# MainSch.net
KiCad netlist of a schematic drawn in Altium Designer
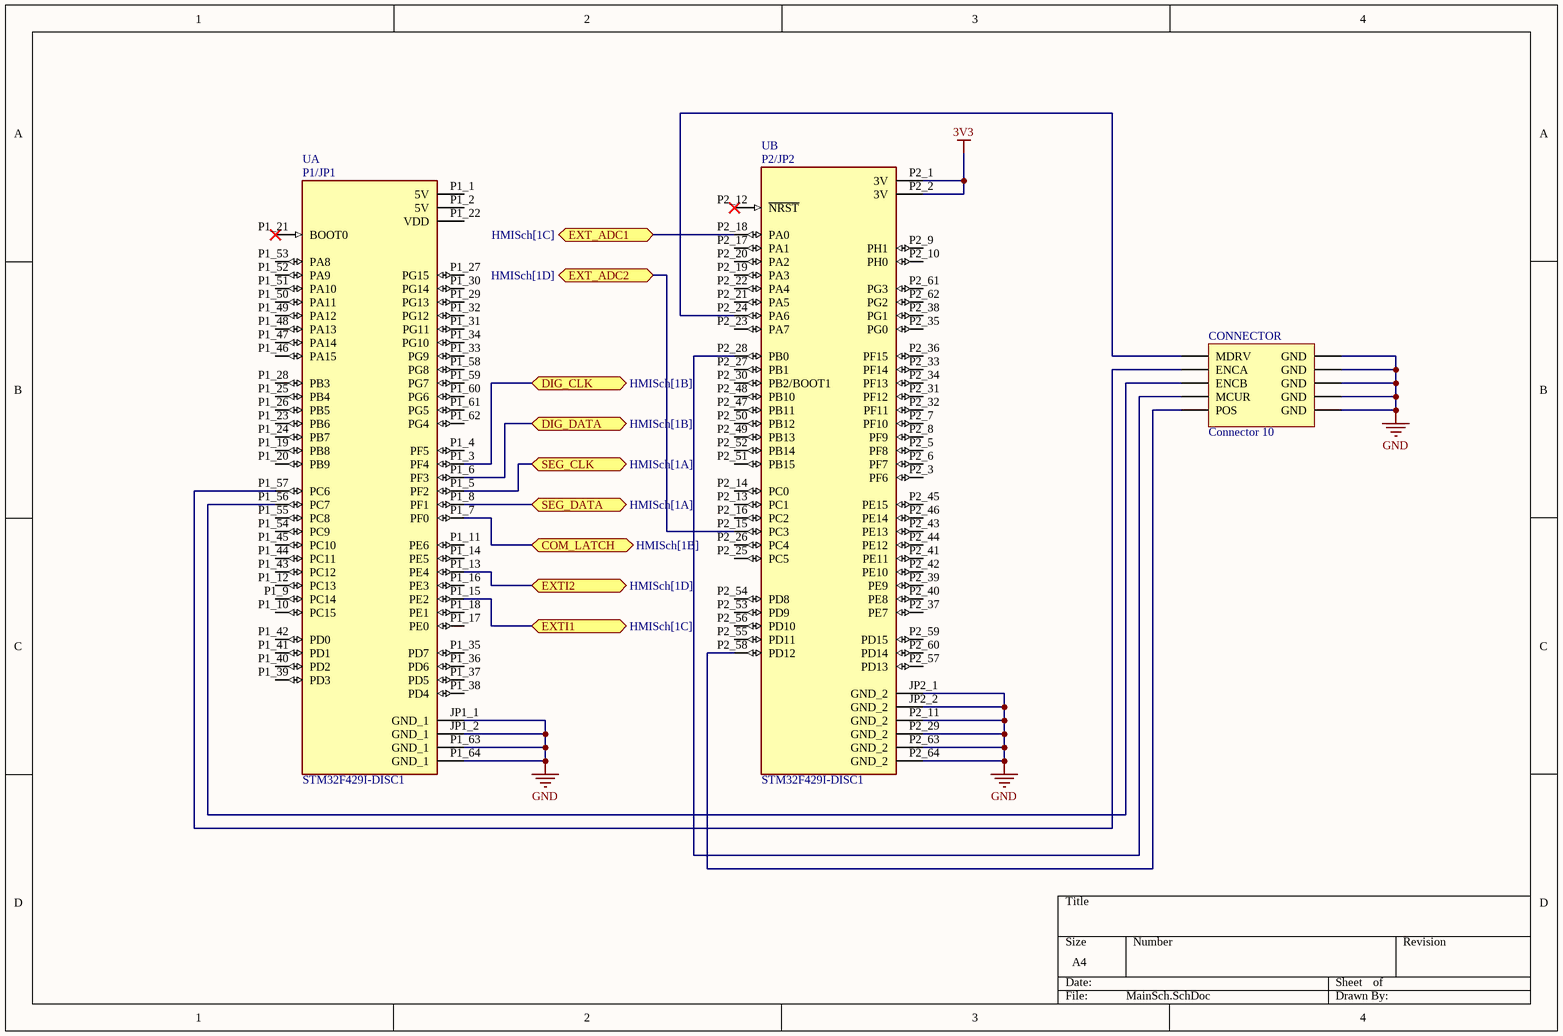
[diagram p0: MainSch.SchDoc]

(export (version "E")
  (design (tool "Eeschema 10.0.6"))
  (components
    (comp (ref "CONNECTOR")
      (value "Connector 10")
      (footprint "CONNECTOR-10P")
      (description "Special 10 pin ribbon connector")
      (libsource (lib "hallglib") (part "Connector 10 spec"))
    )
    (comp (ref "U")
      (value "STM32F429I-DISC1")
      (footprint "MODULE_STM32F429I-DISC1")
      (description "STM32F429 Discovery STM32F4 ARMÂ® CortexÂ®-M4 MCU 32-Bit Embedded Evaluation Board")
      (fields (field (name "MF") "STMicroelectronics"))
      (libsource (lib "SnapEDAsch") (part "STM32F429I-DISC1"))
    )
  )
  (nets
    (net (code "1") (name "/COM_LATCH") (class "Default")
      (node (ref "U") (pin "P1_7") (pinfunction "PF0_P1_7") (pintype "bidirectional"))
    )
    (net (code "2") (name "/DIG_CLK") (class "Default")
      (node (ref "U") (pin "P1_3") (pinfunction "PF4_P1_3") (pintype "bidirectional"))
    )
    (net (code "3") (name "/DIG_DATA") (class "Default")
      (node (ref "U") (pin "P1_6") (pinfunction "PF3_P1_6") (pintype "bidirectional"))
    )
    (net (code "4") (name "/EXTI1") (class "Default")
      (node (ref "U") (pin "P1_15") (pinfunction "PE2_P1_15") (pintype "bidirectional"))
    )
    (net (code "5") (name "/EXTI2") (class "Default")
      (node (ref "U") (pin "P1_13") (pinfunction "PE4_P1_13") (pintype "bidirectional"))
    )
    (net (code "6") (name "/EXT_ADC1") (class "Default")
      (node (ref "U") (pin "P2_18") (pinfunction "PA0_P2_18") (pintype "bidirectional"))
    )
    (net (code "7") (name "/EXT_ADC2") (class "Default")
      (node (ref "U") (pin "P2_15") (pinfunction "PC3_P2_15") (pintype "bidirectional"))
    )
    (net (code "8") (name "/SEG_CLK") (class "Default")
      (node (ref "U") (pin "P1_5") (pinfunction "PF2_P1_5") (pintype "bidirectional"))
    )
    (net (code "9") (name "/SEG_DATA") (class "Default")
      (node (ref "U") (pin "P1_8") (pinfunction "PF1_P1_8") (pintype "bidirectional"))
    )
    (net (code "10") (name "3V3") (class "Default")
      (node (ref "U") (pin "P2_1") (pinfunction "3V_P2_1") (pintype "power_in"))
      (node (ref "U") (pin "P2_2") (pinfunction "3V_P2_2") (pintype "power_in"))
    )
    (net (code "11") (name "GND") (class "Default")
      (node (ref "CONNECTOR") (pin "10") (pinfunction "GND_10") (pintype "passive"))
      (node (ref "CONNECTOR") (pin "2") (pinfunction "GND_2") (pintype "passive"))
      (node (ref "CONNECTOR") (pin "4") (pinfunction "GND_4") (pintype "passive"))
      (node (ref "CONNECTOR") (pin "6") (pinfunction "GND_6") (pintype "passive"))
      (node (ref "CONNECTOR") (pin "8") (pinfunction "GND_8") (pintype "passive"))
      (node (ref "U") (pin "JP1_1") (pinfunction "GND_1_JP1_1") (pintype "power_in"))
      (node (ref "U") (pin "JP1_2") (pinfunction "GND_1_JP1_2") (pintype "power_in"))
      (node (ref "U") (pin "JP2_1") (pinfunction "GND_2_JP2_1") (pintype "power_in"))
      (node (ref "U") (pin "JP2_2") (pinfunction "GND_2_JP2_2") (pintype "power_in"))
      (node (ref "U") (pin "P1_63") (pinfunction "GND_1_P1_63") (pintype "power_in"))
      (node (ref "U") (pin "P1_64") (pinfunction "GND_1_P1_64") (pintype "power_in"))
      (node (ref "U") (pin "P2_11") (pinfunction "GND_2_P2_11") (pintype "power_in"))
      (node (ref "U") (pin "P2_29") (pinfunction "GND_2_P2_29") (pintype "power_in"))
      (node (ref "U") (pin "P2_63") (pinfunction "GND_2_P2_63") (pintype "power_in"))
      (node (ref "U") (pin "P2_64") (pinfunction "GND_2_P2_64") (pintype "power_in"))
    )
    (net (code "12") (name "Net-(CONNECTOR-ENCA)") (class "Default")
      (node (ref "CONNECTOR") (pin "3") (pinfunction "ENCA_3") (pintype "passive"))
      (node (ref "U") (pin "P1_57") (pinfunction "PC6_P1_57") (pintype "bidirectional"))
    )
    (net (code "13") (name "Net-(CONNECTOR-ENCB)") (class "Default")
      (node (ref "CONNECTOR") (pin "5") (pinfunction "ENCB_5") (pintype "passive"))
      (node (ref "U") (pin "P1_56") (pinfunction "PC7_P1_56") (pintype "bidirectional"))
    )
    (net (code "14") (name "Net-(CONNECTOR-MCUR)") (class "Default")
      (node (ref "CONNECTOR") (pin "7") (pinfunction "MCUR_7") (pintype "passive"))
      (node (ref "U") (pin "P2_28") (pinfunction "PB0_P2_28") (pintype "bidirectional"))
    )
    (net (code "15") (name "Net-(CONNECTOR-MDRV)") (class "Default")
      (node (ref "CONNECTOR") (pin "1") (pinfunction "MDRV_1") (pintype "passive"))
      (node (ref "U") (pin "P2_24") (pinfunction "PA6_P2_24") (pintype "bidirectional"))
    )
    (net (code "16") (name "Net-(CONNECTOR-POS)") (class "Default")
      (node (ref "CONNECTOR") (pin "9") (pinfunction "POS_9") (pintype "passive"))
      (node (ref "U") (pin "P2_58") (pinfunction "PD12_P2_58") (pintype "bidirectional"))
    )
    (net (code "17") (name "unconnected-(UA-5V-PadP1_1)") (class "Default")
      (node (ref "U") (pin "P1_1") (pinfunction "5V_P1_1") (pintype "power_in"))
    )
    (net (code "18") (name "unconnected-(UA-5V-PadP1_2)") (class "Default")
      (node (ref "U") (pin "P1_2") (pinfunction "5V_P1_2") (pintype "power_in"))
    )
    (net (code "19") (name "unconnected-(UA-BOOT0-PadP1_21)") (class "Default")
      (node (ref "U") (pin "P1_21") (pinfunction "BOOT0_P1_21") (pintype "input+no_connect"))
    )
    (net (code "20") (name "unconnected-(UA-PA8-PadP1_53)") (class "Default")
      (node (ref "U") (pin "P1_53") (pinfunction "PA8_P1_53") (pintype "bidirectional"))
    )
    (net (code "21") (name "unconnected-(UA-PA9-PadP1_52)") (class "Default")
      (node (ref "U") (pin "P1_52") (pinfunction "PA9_P1_52") (pintype "bidirectional"))
    )
    (net (code "22") (name "unconnected-(UA-PA10-PadP1_51)") (class "Default")
      (node (ref "U") (pin "P1_51") (pinfunction "PA10_P1_51") (pintype "bidirectional"))
    )
    (net (code "23") (name "unconnected-(UA-PA11-PadP1_50)") (class "Default")
      (node (ref "U") (pin "P1_50") (pinfunction "PA11_P1_50") (pintype "bidirectional"))
    )
    (net (code "24") (name "unconnected-(UA-PA12-PadP1_49)") (class "Default")
      (node (ref "U") (pin "P1_49") (pinfunction "PA12_P1_49") (pintype "bidirectional"))
    )
    (net (code "25") (name "unconnected-(UA-PA13-PadP1_48)") (class "Default")
      (node (ref "U") (pin "P1_48") (pinfunction "PA13_P1_48") (pintype "bidirectional"))
    )
    (net (code "26") (name "unconnected-(UA-PA14-PadP1_47)") (class "Default")
      (node (ref "U") (pin "P1_47") (pinfunction "PA14_P1_47") (pintype "bidirectional"))
    )
    (net (code "27") (name "unconnected-(UA-PA15-PadP1_46)") (class "Default")
      (node (ref "U") (pin "P1_46") (pinfunction "PA15_P1_46") (pintype "bidirectional"))
    )
    (net (code "28") (name "unconnected-(UA-PB3-PadP1_28)") (class "Default")
      (node (ref "U") (pin "P1_28") (pinfunction "PB3_P1_28") (pintype "bidirectional"))
    )
    (net (code "29") (name "unconnected-(UA-PB4-PadP1_25)") (class "Default")
      (node (ref "U") (pin "P1_25") (pinfunction "PB4_P1_25") (pintype "bidirectional"))
    )
    (net (code "30") (name "unconnected-(UA-PB5-PadP1_26)") (class "Default")
      (node (ref "U") (pin "P1_26") (pinfunction "PB5_P1_26") (pintype "bidirectional"))
    )
    (net (code "31") (name "unconnected-(UA-PB6-PadP1_23)") (class "Default")
      (node (ref "U") (pin "P1_23") (pinfunction "PB6_P1_23") (pintype "bidirectional"))
    )
    (net (code "32") (name "unconnected-(UA-PB7-PadP1_24)") (class "Default")
      (node (ref "U") (pin "P1_24") (pinfunction "PB7_P1_24") (pintype "bidirectional"))
    )
    (net (code "33") (name "unconnected-(UA-PB8-PadP1_19)") (class "Default")
      (node (ref "U") (pin "P1_19") (pinfunction "PB8_P1_19") (pintype "bidirectional"))
    )
    (net (code "34") (name "unconnected-(UA-PB9-PadP1_20)") (class "Default")
      (node (ref "U") (pin "P1_20") (pinfunction "PB9_P1_20") (pintype "bidirectional"))
    )
    (net (code "35") (name "unconnected-(UA-PC8-PadP1_55)") (class "Default")
      (node (ref "U") (pin "P1_55") (pinfunction "PC8_P1_55") (pintype "bidirectional"))
    )
    (net (code "36") (name "unconnected-(UA-PC9-PadP1_54)") (class "Default")
      (node (ref "U") (pin "P1_54") (pinfunction "PC9_P1_54") (pintype "bidirectional"))
    )
    (net (code "37") (name "unconnected-(UA-PC10-PadP1_45)") (class "Default")
      (node (ref "U") (pin "P1_45") (pinfunction "PC10_P1_45") (pintype "bidirectional"))
    )
    (net (code "38") (name "unconnected-(UA-PC11-PadP1_44)") (class "Default")
      (node (ref "U") (pin "P1_44") (pinfunction "PC11_P1_44") (pintype "bidirectional"))
    )
    (net (code "39") (name "unconnected-(UA-PC12-PadP1_43)") (class "Default")
      (node (ref "U") (pin "P1_43") (pinfunction "PC12_P1_43") (pintype "bidirectional"))
    )
    (net (code "40") (name "unconnected-(UA-PC13-PadP1_12)") (class "Default")
      (node (ref "U") (pin "P1_12") (pinfunction "PC13_P1_12") (pintype "bidirectional"))
    )
    (net (code "41") (name "unconnected-(UA-PC14-PadP1_9)") (class "Default")
      (node (ref "U") (pin "P1_9") (pinfunction "PC14_P1_9") (pintype "bidirectional"))
    )
    (net (code "42") (name "unconnected-(UA-PC15-PadP1_10)") (class "Default")
      (node (ref "U") (pin "P1_10") (pinfunction "PC15_P1_10") (pintype "bidirectional"))
    )
    (net (code "43") (name "unconnected-(UA-PD0-PadP1_42)") (class "Default")
      (node (ref "U") (pin "P1_42") (pinfunction "PD0_P1_42") (pintype "bidirectional"))
    )
    (net (code "44") (name "unconnected-(UA-PD1-PadP1_41)") (class "Default")
      (node (ref "U") (pin "P1_41") (pinfunction "PD1_P1_41") (pintype "bidirectional"))
    )
    (net (code "45") (name "unconnected-(UA-PD2-PadP1_40)") (class "Default")
      (node (ref "U") (pin "P1_40") (pinfunction "PD2_P1_40") (pintype "bidirectional"))
    )
    (net (code "46") (name "unconnected-(UA-PD3-PadP1_39)") (class "Default")
      (node (ref "U") (pin "P1_39") (pinfunction "PD3_P1_39") (pintype "bidirectional"))
    )
    (net (code "47") (name "unconnected-(UA-PD4-PadP1_38)") (class "Default")
      (node (ref "U") (pin "P1_38") (pinfunction "PD4_P1_38") (pintype "bidirectional"))
    )
    (net (code "48") (name "unconnected-(UA-PD5-PadP1_37)") (class "Default")
      (node (ref "U") (pin "P1_37") (pinfunction "PD5_P1_37") (pintype "bidirectional"))
    )
    (net (code "49") (name "unconnected-(UA-PD6-PadP1_36)") (class "Default")
      (node (ref "U") (pin "P1_36") (pinfunction "PD6_P1_36") (pintype "bidirectional"))
    )
    (net (code "50") (name "unconnected-(UA-PD7-PadP1_35)") (class "Default")
      (node (ref "U") (pin "P1_35") (pinfunction "PD7_P1_35") (pintype "bidirectional"))
    )
    (net (code "51") (name "unconnected-(UA-PE0-PadP1_17)") (class "Default")
      (node (ref "U") (pin "P1_17") (pinfunction "PE0_P1_17") (pintype "bidirectional"))
    )
    (net (code "52") (name "unconnected-(UA-PE1-PadP1_18)") (class "Default")
      (node (ref "U") (pin "P1_18") (pinfunction "PE1_P1_18") (pintype "bidirectional"))
    )
    (net (code "53") (name "unconnected-(UA-PE3-PadP1_16)") (class "Default")
      (node (ref "U") (pin "P1_16") (pinfunction "PE3_P1_16") (pintype "bidirectional"))
    )
    (net (code "54") (name "unconnected-(UA-PE5-PadP1_14)") (class "Default")
      (node (ref "U") (pin "P1_14") (pinfunction "PE5_P1_14") (pintype "bidirectional"))
    )
    (net (code "55") (name "unconnected-(UA-PE6-PadP1_11)") (class "Default")
      (node (ref "U") (pin "P1_11") (pinfunction "PE6_P1_11") (pintype "bidirectional"))
    )
    (net (code "56") (name "unconnected-(UA-PF5-PadP1_4)") (class "Default")
      (node (ref "U") (pin "P1_4") (pinfunction "PF5_P1_4") (pintype "bidirectional"))
    )
    (net (code "57") (name "unconnected-(UA-PG4-PadP1_62)") (class "Default")
      (node (ref "U") (pin "P1_62") (pinfunction "PG4_P1_62") (pintype "bidirectional"))
    )
    (net (code "58") (name "unconnected-(UA-PG5-PadP1_61)") (class "Default")
      (node (ref "U") (pin "P1_61") (pinfunction "PG5_P1_61") (pintype "bidirectional"))
    )
    (net (code "59") (name "unconnected-(UA-PG6-PadP1_60)") (class "Default")
      (node (ref "U") (pin "P1_60") (pinfunction "PG6_P1_60") (pintype "bidirectional"))
    )
    (net (code "60") (name "unconnected-(UA-PG7-PadP1_59)") (class "Default")
      (node (ref "U") (pin "P1_59") (pinfunction "PG7_P1_59") (pintype "bidirectional"))
    )
    (net (code "61") (name "unconnected-(UA-PG8-PadP1_58)") (class "Default")
      (node (ref "U") (pin "P1_58") (pinfunction "PG8_P1_58") (pintype "bidirectional"))
    )
    (net (code "62") (name "unconnected-(UA-PG9-PadP1_33)") (class "Default")
      (node (ref "U") (pin "P1_33") (pinfunction "PG9_P1_33") (pintype "bidirectional"))
    )
    (net (code "63") (name "unconnected-(UA-PG10-PadP1_34)") (class "Default")
      (node (ref "U") (pin "P1_34") (pinfunction "PG10_P1_34") (pintype "bidirectional"))
    )
    (net (code "64") (name "unconnected-(UA-PG11-PadP1_31)") (class "Default")
      (node (ref "U") (pin "P1_31") (pinfunction "PG11_P1_31") (pintype "bidirectional"))
    )
    (net (code "65") (name "unconnected-(UA-PG12-PadP1_32)") (class "Default")
      (node (ref "U") (pin "P1_32") (pinfunction "PG12_P1_32") (pintype "bidirectional"))
    )
    (net (code "66") (name "unconnected-(UA-PG13-PadP1_29)") (class "Default")
      (node (ref "U") (pin "P1_29") (pinfunction "PG13_P1_29") (pintype "bidirectional"))
    )
    (net (code "67") (name "unconnected-(UA-PG14-PadP1_30)") (class "Default")
      (node (ref "U") (pin "P1_30") (pinfunction "PG14_P1_30") (pintype "bidirectional"))
    )
    (net (code "68") (name "unconnected-(UA-PG15-PadP1_27)") (class "Default")
      (node (ref "U") (pin "P1_27") (pinfunction "PG15_P1_27") (pintype "bidirectional"))
    )
    (net (code "69") (name "unconnected-(UA-VDD-PadP1_22)") (class "Default")
      (node (ref "U") (pin "P1_22") (pinfunction "VDD_P1_22") (pintype "power_in"))
    )
    (net (code "70") (name "unconnected-(UB-PA1-PadP2_17)") (class "Default")
      (node (ref "U") (pin "P2_17") (pinfunction "PA1_P2_17") (pintype "bidirectional"))
    )
    (net (code "71") (name "unconnected-(UB-PA2-PadP2_20)") (class "Default")
      (node (ref "U") (pin "P2_20") (pinfunction "PA2_P2_20") (pintype "bidirectional"))
    )
    (net (code "72") (name "unconnected-(UB-PA3-PadP2_19)") (class "Default")
      (node (ref "U") (pin "P2_19") (pinfunction "PA3_P2_19") (pintype "bidirectional"))
    )
    (net (code "73") (name "unconnected-(UB-PA4-PadP2_22)") (class "Default")
      (node (ref "U") (pin "P2_22") (pinfunction "PA4_P2_22") (pintype "bidirectional"))
    )
    (net (code "74") (name "unconnected-(UB-PA5-PadP2_21)") (class "Default")
      (node (ref "U") (pin "P2_21") (pinfunction "PA5_P2_21") (pintype "bidirectional"))
    )
    (net (code "75") (name "unconnected-(UB-PA7-PadP2_23)") (class "Default")
      (node (ref "U") (pin "P2_23") (pinfunction "PA7_P2_23") (pintype "bidirectional"))
    )
    (net (code "76") (name "unconnected-(UB-PB1-PadP2_27)") (class "Default")
      (node (ref "U") (pin "P2_27") (pinfunction "PB1_P2_27") (pintype "bidirectional"))
    )
    (net (code "77") (name "unconnected-(UB-PB2{slash}BOOT1-PadP2_30)") (class "Default")
      (node (ref "U") (pin "P2_30") (pinfunction "PB2/BOOT1_P2_30") (pintype "bidirectional"))
    )
    (net (code "78") (name "unconnected-(UB-PB10-PadP2_48)") (class "Default")
      (node (ref "U") (pin "P2_48") (pinfunction "PB10_P2_48") (pintype "bidirectional"))
    )
    (net (code "79") (name "unconnected-(UB-PB11-PadP2_47)") (class "Default")
      (node (ref "U") (pin "P2_47") (pinfunction "PB11_P2_47") (pintype "bidirectional"))
    )
    (net (code "80") (name "unconnected-(UB-PB12-PadP2_50)") (class "Default")
      (node (ref "U") (pin "P2_50") (pinfunction "PB12_P2_50") (pintype "bidirectional"))
    )
    (net (code "81") (name "unconnected-(UB-PB13-PadP2_49)") (class "Default")
      (node (ref "U") (pin "P2_49") (pinfunction "PB13_P2_49") (pintype "bidirectional"))
    )
    (net (code "82") (name "unconnected-(UB-PB14-PadP2_52)") (class "Default")
      (node (ref "U") (pin "P2_52") (pinfunction "PB14_P2_52") (pintype "bidirectional"))
    )
    (net (code "83") (name "unconnected-(UB-PB15-PadP2_51)") (class "Default")
      (node (ref "U") (pin "P2_51") (pinfunction "PB15_P2_51") (pintype "bidirectional"))
    )
    (net (code "84") (name "unconnected-(UB-PC0-PadP2_14)") (class "Default")
      (node (ref "U") (pin "P2_14") (pinfunction "PC0_P2_14") (pintype "bidirectional"))
    )
    (net (code "85") (name "unconnected-(UB-PC1-PadP2_13)") (class "Default")
      (node (ref "U") (pin "P2_13") (pinfunction "PC1_P2_13") (pintype "bidirectional"))
    )
    (net (code "86") (name "unconnected-(UB-PC2-PadP2_16)") (class "Default")
      (node (ref "U") (pin "P2_16") (pinfunction "PC2_P2_16") (pintype "bidirectional"))
    )
    (net (code "87") (name "unconnected-(UB-PC4-PadP2_26)") (class "Default")
      (node (ref "U") (pin "P2_26") (pinfunction "PC4_P2_26") (pintype "bidirectional"))
    )
    (net (code "88") (name "unconnected-(UB-PC5-PadP2_25)") (class "Default")
      (node (ref "U") (pin "P2_25") (pinfunction "PC5_P2_25") (pintype "bidirectional"))
    )
    (net (code "89") (name "unconnected-(UB-PD8-PadP2_54)") (class "Default")
      (node (ref "U") (pin "P2_54") (pinfunction "PD8_P2_54") (pintype "bidirectional"))
    )
    (net (code "90") (name "unconnected-(UB-PD9-PadP2_53)") (class "Default")
      (node (ref "U") (pin "P2_53") (pinfunction "PD9_P2_53") (pintype "bidirectional"))
    )
    (net (code "91") (name "unconnected-(UB-PD10-PadP2_56)") (class "Default")
      (node (ref "U") (pin "P2_56") (pinfunction "PD10_P2_56") (pintype "bidirectional"))
    )
    (net (code "92") (name "unconnected-(UB-PD11-PadP2_55)") (class "Default")
      (node (ref "U") (pin "P2_55") (pinfunction "PD11_P2_55") (pintype "bidirectional"))
    )
    (net (code "93") (name "unconnected-(UB-PD13-PadP2_57)") (class "Default")
      (node (ref "U") (pin "P2_57") (pinfunction "PD13_P2_57") (pintype "bidirectional"))
    )
    (net (code "94") (name "unconnected-(UB-PD14-PadP2_60)") (class "Default")
      (node (ref "U") (pin "P2_60") (pinfunction "PD14_P2_60") (pintype "bidirectional"))
    )
    (net (code "95") (name "unconnected-(UB-PD15-PadP2_59)") (class "Default")
      (node (ref "U") (pin "P2_59") (pinfunction "PD15_P2_59") (pintype "bidirectional"))
    )
    (net (code "96") (name "unconnected-(UB-PE7-PadP2_37)") (class "Default")
      (node (ref "U") (pin "P2_37") (pinfunction "PE7_P2_37") (pintype "bidirectional"))
    )
    (net (code "97") (name "unconnected-(UB-PE8-PadP2_40)") (class "Default")
      (node (ref "U") (pin "P2_40") (pinfunction "PE8_P2_40") (pintype "bidirectional"))
    )
    (net (code "98") (name "unconnected-(UB-PE9-PadP2_39)") (class "Default")
      (node (ref "U") (pin "P2_39") (pinfunction "PE9_P2_39") (pintype "bidirectional"))
    )
    (net (code "99") (name "unconnected-(UB-PE10-PadP2_42)") (class "Default")
      (node (ref "U") (pin "P2_42") (pinfunction "PE10_P2_42") (pintype "bidirectional"))
    )
    (net (code "100") (name "unconnected-(UB-PE11-PadP2_41)") (class "Default")
      (node (ref "U") (pin "P2_41") (pinfunction "PE11_P2_41") (pintype "bidirectional"))
    )
    (net (code "101") (name "unconnected-(UB-PE12-PadP2_44)") (class "Default")
      (node (ref "U") (pin "P2_44") (pinfunction "PE12_P2_44") (pintype "bidirectional"))
    )
    (net (code "102") (name "unconnected-(UB-PE13-PadP2_43)") (class "Default")
      (node (ref "U") (pin "P2_43") (pinfunction "PE13_P2_43") (pintype "bidirectional"))
    )
    (net (code "103") (name "unconnected-(UB-PE14-PadP2_46)") (class "Default")
      (node (ref "U") (pin "P2_46") (pinfunction "PE14_P2_46") (pintype "bidirectional"))
    )
    (net (code "104") (name "unconnected-(UB-PE15-PadP2_45)") (class "Default")
      (node (ref "U") (pin "P2_45") (pinfunction "PE15_P2_45") (pintype "bidirectional"))
    )
    (net (code "105") (name "unconnected-(UB-PF6-PadP2_3)") (class "Default")
      (node (ref "U") (pin "P2_3") (pinfunction "PF6_P2_3") (pintype "bidirectional"))
    )
    (net (code "106") (name "unconnected-(UB-PF7-PadP2_6)") (class "Default")
      (node (ref "U") (pin "P2_6") (pinfunction "PF7_P2_6") (pintype "bidirectional"))
    )
    (net (code "107") (name "unconnected-(UB-PF8-PadP2_5)") (class "Default")
      (node (ref "U") (pin "P2_5") (pinfunction "PF8_P2_5") (pintype "bidirectional"))
    )
    (net (code "108") (name "unconnected-(UB-PF9-PadP2_8)") (class "Default")
      (node (ref "U") (pin "P2_8") (pinfunction "PF9_P2_8") (pintype "bidirectional"))
    )
    (net (code "109") (name "unconnected-(UB-PF10-PadP2_7)") (class "Default")
      (node (ref "U") (pin "P2_7") (pinfunction "PF10_P2_7") (pintype "bidirectional"))
    )
    (net (code "110") (name "unconnected-(UB-PF11-PadP2_32)") (class "Default")
      (node (ref "U") (pin "P2_32") (pinfunction "PF11_P2_32") (pintype "bidirectional"))
    )
    (net (code "111") (name "unconnected-(UB-PF12-PadP2_31)") (class "Default")
      (node (ref "U") (pin "P2_31") (pinfunction "PF12_P2_31") (pintype "bidirectional"))
    )
    (net (code "112") (name "unconnected-(UB-PF13-PadP2_34)") (class "Default")
      (node (ref "U") (pin "P2_34") (pinfunction "PF13_P2_34") (pintype "bidirectional"))
    )
    (net (code "113") (name "unconnected-(UB-PF14-PadP2_33)") (class "Default")
      (node (ref "U") (pin "P2_33") (pinfunction "PF14_P2_33") (pintype "bidirectional"))
    )
    (net (code "114") (name "unconnected-(UB-PF15-PadP2_36)") (class "Default")
      (node (ref "U") (pin "P2_36") (pinfunction "PF15_P2_36") (pintype "bidirectional"))
    )
    (net (code "115") (name "unconnected-(UB-PG0-PadP2_35)") (class "Default")
      (node (ref "U") (pin "P2_35") (pinfunction "PG0_P2_35") (pintype "bidirectional"))
    )
    (net (code "116") (name "unconnected-(UB-PG1-PadP2_38)") (class "Default")
      (node (ref "U") (pin "P2_38") (pinfunction "PG1_P2_38") (pintype "bidirectional"))
    )
    (net (code "117") (name "unconnected-(UB-PG2-PadP2_62)") (class "Default")
      (node (ref "U") (pin "P2_62") (pinfunction "PG2_P2_62") (pintype "bidirectional"))
    )
    (net (code "118") (name "unconnected-(UB-PG3-PadP2_61)") (class "Default")
      (node (ref "U") (pin "P2_61") (pinfunction "PG3_P2_61") (pintype "bidirectional"))
    )
    (net (code "119") (name "unconnected-(UB-PH0-PadP2_10)") (class "Default")
      (node (ref "U") (pin "P2_10") (pinfunction "PH0_P2_10") (pintype "bidirectional"))
    )
    (net (code "120") (name "unconnected-(UB-PH1-PadP2_9)") (class "Default")
      (node (ref "U") (pin "P2_9") (pinfunction "PH1_P2_9") (pintype "bidirectional"))
    )
    (net (code "121") (name "unconnected-(UB-~{NRST}-PadP2_12)") (class "Default")
      (node (ref "U") (pin "P2_12") (pinfunction "~{NRST}_P2_12") (pintype "input+no_connect"))
    )
  )
)
